# OptoBoard.net
KiCad netlist of a schematic drawn in Altium Designer
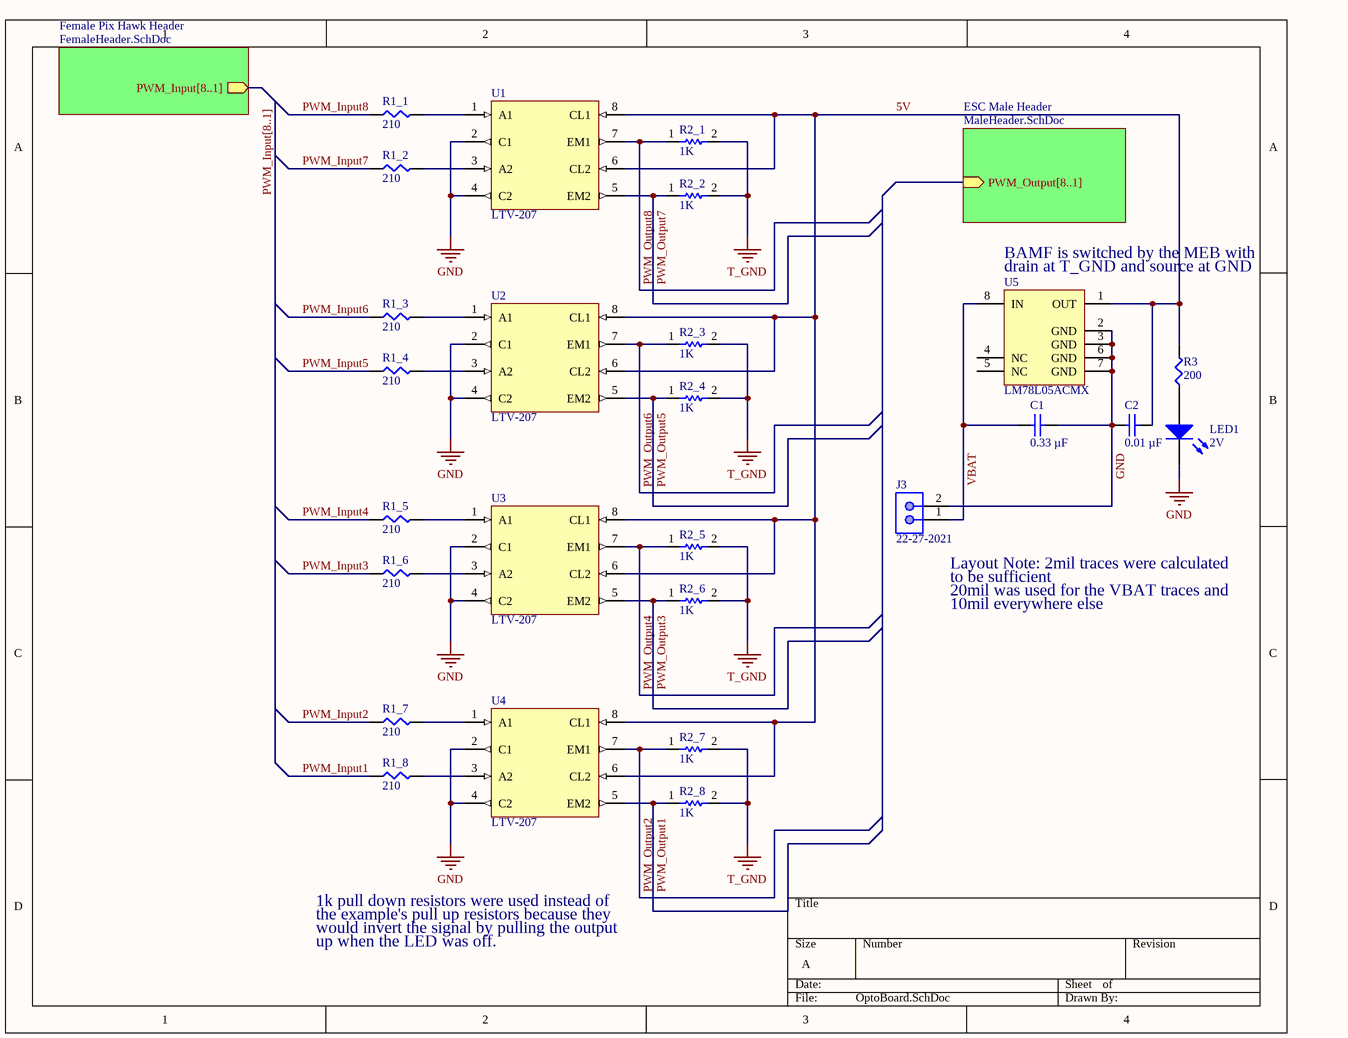
[diagram p0: OptoBoard.SchDoc]

(export (version "E")
  (design (tool "Eeschema 10.0.6"))
  (components
    (comp (ref "C1")
      (value "0.33 µF")
      (footprint "CAPC2013X95X45ML10T25")
      (description "±10% 50V Ceramic Capacitor X7R 0805 (2012 Metric)")
      (fields (field (name "MANUFACTURER") "Murata") (field (name "PART NUMBER") "GRM219R71H334KA88D"))
      (libsource (lib "Altium Content Vault") (part "CAP"))
    )
    (comp (ref "C2")
      (value "0.01 µF")
      (footprint "CAPC2013X70X45LL15T25")
      (description "±10% 100V Ceramic Capacitor X7R 0805 (2012 Metric)")
      (fields (field (name "MANUFACTURER") "Murata") (field (name "PART NUMBER") "GCM216R72A103KA37D"))
      (libsource (lib "Altium Content Vault") (part "CAP"))
    )
    (comp (ref "J3")
      (value "22-27-2021")
      (footprint "MOLX-22-27-2021_V")
      (fields
        (field (name "MANUFACTURER") "Molex")
        (field (name "PARTNUMBER") "0022272021")
        (field (name "MANUFACTURER PART NUMBER") "AE-6410-2A")
      )
      (libsource (lib "Altium Content Vault") (part "CN-1P-M-R2"))
    )
    (comp (ref "LED1")
      (value "2V")
      (footprint "1206  CYLINDRICAL- Reverse Use")
      (description "SMD mono-color reverse mount waterclear Chip LED, WL-SMRW, Red, 156120RS75300")
      (fields (field (name "MANUFACTURER") "Wuerth Elektronik") (field (name "PARTNUMBER") "156120RS75300"))
      (libsource (lib "Altium Content Vault") (part "WE-LED_K1A2-2"))
    )
    (comp (ref "R1_1")
      (value "210")
      (footprint "SMD-0805-RES")
      (description "RES SMD 210 OHM 1% 1/8W 0805")
      (fields (field (name "PART NUMBER") "ERJ-6ENF2100V") (field (name "DIGI-KEY PART NUMBER") "P210CCT-ND"))
      (libsource (lib "Panasonic_resistor_0805") (part "ERJ-6ENF2100V"))
    )
    (comp (ref "R1_2")
      (value "210")
      (footprint "SMD-0805-RES")
      (description "RES SMD 210 OHM 1% 1/8W 0805")
      (fields (field (name "PART NUMBER") "ERJ-6ENF2100V") (field (name "DIGI-KEY PART NUMBER") "P210CCT-ND"))
      (libsource (lib "Panasonic_resistor_0805") (part "ERJ-6ENF2100V"))
    )
    (comp (ref "R1_3")
      (value "210")
      (footprint "SMD-0805-RES")
      (description "RES SMD 210 OHM 1% 1/8W 0805")
      (fields (field (name "PART NUMBER") "ERJ-6ENF2100V") (field (name "DIGI-KEY PART NUMBER") "P210CCT-ND"))
      (libsource (lib "Panasonic_resistor_0805") (part "ERJ-6ENF2100V"))
    )
    (comp (ref "R1_4")
      (value "210")
      (footprint "SMD-0805-RES")
      (description "RES SMD 210 OHM 1% 1/8W 0805")
      (fields (field (name "PART NUMBER") "ERJ-6ENF2100V") (field (name "DIGI-KEY PART NUMBER") "P210CCT-ND"))
      (libsource (lib "Panasonic_resistor_0805") (part "ERJ-6ENF2100V"))
    )
    (comp (ref "R1_5")
      (value "210")
      (footprint "SMD-0805-RES")
      (description "RES SMD 210 OHM 1% 1/8W 0805")
      (fields (field (name "PART NUMBER") "ERJ-6ENF2100V") (field (name "DIGI-KEY PART NUMBER") "P210CCT-ND"))
      (libsource (lib "Panasonic_resistor_0805") (part "ERJ-6ENF2100V"))
    )
    (comp (ref "R1_6")
      (value "210")
      (footprint "SMD-0805-RES")
      (description "RES SMD 210 OHM 1% 1/8W 0805")
      (fields (field (name "PART NUMBER") "ERJ-6ENF2100V") (field (name "DIGI-KEY PART NUMBER") "P210CCT-ND"))
      (libsource (lib "Panasonic_resistor_0805") (part "ERJ-6ENF2100V"))
    )
    (comp (ref "R1_7")
      (value "210")
      (footprint "SMD-0805-RES")
      (description "RES SMD 210 OHM 1% 1/8W 0805")
      (fields (field (name "PART NUMBER") "ERJ-6ENF2100V") (field (name "DIGI-KEY PART NUMBER") "P210CCT-ND"))
      (libsource (lib "Panasonic_resistor_0805") (part "ERJ-6ENF2100V"))
    )
    (comp (ref "R1_8")
      (value "210")
      (footprint "SMD-0805-RES")
      (description "RES SMD 210 OHM 1% 1/8W 0805")
      (fields (field (name "PART NUMBER") "ERJ-6ENF2100V") (field (name "DIGI-KEY PART NUMBER") "P210CCT-ND"))
      (libsource (lib "Panasonic_resistor_0805") (part "ERJ-6ENF2100V"))
    )
    (comp (ref "R2_1")
      (value "1K")
      (footprint "RESC2013X60X35ML10T20")
      (description "Chip Resistor, 1 KOhm, +/- 1%, 125 mW, -55 to 155 degC, 0805 (2012 Metric), RoHS, Tape and Reel")
      (fields (field (name "TOLERANCE") "1%") (field (name "MANUFACTURER") "Yageo"))
      (libsource (lib "Altium Content Vault") (part "RES-2"))
    )
    (comp (ref "R2_2")
      (value "1K")
      (footprint "RESC2013X60X35ML10T20")
      (description "Chip Resistor, 1 KOhm, +/- 1%, 125 mW, -55 to 155 degC, 0805 (2012 Metric), RoHS, Tape and Reel")
      (fields (field (name "TOLERANCE") "1%") (field (name "MANUFACTURER") "Yageo"))
      (libsource (lib "Altium Content Vault") (part "RES-2"))
    )
    (comp (ref "R2_3")
      (value "1K")
      (footprint "RESC2013X60X35ML10T20")
      (description "Chip Resistor, 1 KOhm, +/- 1%, 125 mW, -55 to 155 degC, 0805 (2012 Metric), RoHS, Tape and Reel")
      (fields (field (name "TOLERANCE") "1%") (field (name "MANUFACTURER") "Yageo"))
      (libsource (lib "Altium Content Vault") (part "RES-2"))
    )
    (comp (ref "R2_4")
      (value "1K")
      (footprint "RESC2013X60X35ML10T20")
      (description "Chip Resistor, 1 KOhm, +/- 1%, 125 mW, -55 to 155 degC, 0805 (2012 Metric), RoHS, Tape and Reel")
      (fields (field (name "TOLERANCE") "1%") (field (name "MANUFACTURER") "Yageo"))
      (libsource (lib "Altium Content Vault") (part "RES-2"))
    )
    (comp (ref "R2_5")
      (value "1K")
      (footprint "RESC2013X60X35ML10T20")
      (description "Chip Resistor, 1 KOhm, +/- 1%, 125 mW, -55 to 155 degC, 0805 (2012 Metric), RoHS, Tape and Reel")
      (fields (field (name "TOLERANCE") "1%") (field (name "MANUFACTURER") "Yageo"))
      (libsource (lib "Altium Content Vault") (part "RES-2"))
    )
    (comp (ref "R2_6")
      (value "1K")
      (footprint "RESC2013X60X35ML10T20")
      (description "Chip Resistor, 1 KOhm, +/- 1%, 125 mW, -55 to 155 degC, 0805 (2012 Metric), RoHS, Tape and Reel")
      (fields (field (name "TOLERANCE") "1%") (field (name "MANUFACTURER") "Yageo"))
      (libsource (lib "Altium Content Vault") (part "RES-2"))
    )
    (comp (ref "R2_7")
      (value "1K")
      (footprint "RESC2013X60X35ML10T20")
      (description "Chip Resistor, 1 KOhm, +/- 1%, 125 mW, -55 to 155 degC, 0805 (2012 Metric), RoHS, Tape and Reel")
      (fields (field (name "TOLERANCE") "1%") (field (name "MANUFACTURER") "Yageo"))
      (libsource (lib "Altium Content Vault") (part "RES-2"))
    )
    (comp (ref "R2_8")
      (value "1K")
      (footprint "RESC2013X60X35ML10T20")
      (description "Chip Resistor, 1 KOhm, +/- 1%, 125 mW, -55 to 155 degC, 0805 (2012 Metric), RoHS, Tape and Reel")
      (fields (field (name "TOLERANCE") "1%") (field (name "MANUFACTURER") "Yageo"))
      (libsource (lib "Altium Content Vault") (part "RES-2"))
    )
    (comp (ref "R3")
      (value "200")
      (footprint "SMD-0805-RES")
      (description "RES SMD 200 OHM 1% 1/8W 0805")
      (fields (field (name "PART NUMBER") "ERJ-6ENF2000V") (field (name "DIGI-KEY PART NUMBER") "P200CCT-ND"))
      (libsource (lib "Panasonic_resistor_0805") (part "ERJ-6ENF2000V"))
    )
    (comp (ref "U1")
      (value "LTV-207")
      (footprint "ZMDI-SOP-8_N")
      (description "Transistor Output Optocouplers SO8 100-200% 3.75KV 2CH Optocoupler")
      (fields (field (name "MANUFACTURER") "Lite-On Inc."))
      (libsource (lib "Altium Content Vault") (part "ZMDI-ZLED7010-SOP8"))
    )
    (comp (ref "U2")
      (value "LTV-207")
      (footprint "ZMDI-SOP-8_N")
      (description "Transistor Output Optocouplers SO8 100-200% 3.75KV 2CH Optocoupler")
      (fields (field (name "MANUFACTURER") "Lite-On Inc."))
      (libsource (lib "Altium Content Vault") (part "ZMDI-ZLED7010-SOP8"))
    )
    (comp (ref "U3")
      (value "LTV-207")
      (footprint "ZMDI-SOP-8_N")
      (description "Transistor Output Optocouplers SO8 100-200% 3.75KV 2CH Optocoupler")
      (fields (field (name "MANUFACTURER") "Lite-On Inc."))
      (libsource (lib "Altium Content Vault") (part "ZMDI-ZLED7010-SOP8"))
    )
    (comp (ref "U4")
      (value "LTV-207")
      (footprint "ZMDI-SOP-8_N")
      (description "Transistor Output Optocouplers SO8 100-200% 3.75KV 2CH Optocoupler")
      (fields (field (name "MANUFACTURER") "Lite-On Inc."))
      (libsource (lib "Altium Content Vault") (part "ZMDI-ZLED7010-SOP8"))
    )
    (comp (ref "U5")
      (value "LM78L05ACMX")
      (footprint "D0008A_N")
      (description "3-Terminal Positive Regulator, 5 Vout, 8-pin Narrow SOIC, 2500 Reel")
      (fields (field (name "MANUFACTURER") "Texas Instruments"))
      (libsource (lib "Altium Content Vault") (part "PM-REG-LM78L05-IL8"))
    )
  )
  (nets
    (net (code "1") (name "/5V") (class "Default")
      (node (ref "C2") (pin "2") (pinfunction "2_2") (pintype "passive"))
      (node (ref "R3") (pin "2") (pinfunction "2_2") (pintype "passive"))
      (node (ref "U1") (pin "6") (pinfunction "CL2_6") (pintype "input"))
      (node (ref "U1") (pin "8") (pinfunction "CL1_8") (pintype "input"))
      (node (ref "U2") (pin "6") (pinfunction "CL2_6") (pintype "input"))
      (node (ref "U2") (pin "8") (pinfunction "CL1_8") (pintype "input"))
      (node (ref "U3") (pin "6") (pinfunction "CL2_6") (pintype "input"))
      (node (ref "U3") (pin "8") (pinfunction "CL1_8") (pintype "input"))
      (node (ref "U4") (pin "6") (pinfunction "CL2_6") (pintype "input"))
      (node (ref "U4") (pin "8") (pinfunction "CL1_8") (pintype "input"))
      (node (ref "U5") (pin "1") (pinfunction "OUT_1") (pintype "power_in"))
    )
    (net (code "2") (name "/PWM_Input1") (class "Default")
      (node (ref "R1_8") (pin "1") (pinfunction "1_1") (pintype "passive"))
    )
    (net (code "3") (name "/PWM_Input2") (class "Default")
      (node (ref "R1_7") (pin "1") (pinfunction "1_1") (pintype "passive"))
    )
    (net (code "4") (name "/PWM_Input3") (class "Default")
      (node (ref "R1_6") (pin "1") (pinfunction "1_1") (pintype "passive"))
    )
    (net (code "5") (name "/PWM_Input4") (class "Default")
      (node (ref "R1_5") (pin "1") (pinfunction "1_1") (pintype "passive"))
    )
    (net (code "6") (name "/PWM_Input5") (class "Default")
      (node (ref "R1_4") (pin "1") (pinfunction "1_1") (pintype "passive"))
    )
    (net (code "7") (name "/PWM_Input6") (class "Default")
      (node (ref "R1_3") (pin "1") (pinfunction "1_1") (pintype "passive"))
    )
    (net (code "8") (name "/PWM_Input7") (class "Default")
      (node (ref "R1_2") (pin "1") (pinfunction "1_1") (pintype "passive"))
    )
    (net (code "9") (name "/PWM_Input8") (class "Default")
      (node (ref "R1_1") (pin "1") (pinfunction "1_1") (pintype "passive"))
    )
    (net (code "11") (name "/PWM_Output1") (class "Default")
      (node (ref "R2_8") (pin "1") (pinfunction "1_1") (pintype "passive"))
      (node (ref "U4") (pin "5") (pinfunction "EM2_5") (pintype "output"))
    )
    (net (code "12") (name "/PWM_Output2") (class "Default")
      (node (ref "R2_7") (pin "1") (pinfunction "1_1") (pintype "passive"))
      (node (ref "U4") (pin "7") (pinfunction "EM1_7") (pintype "output"))
    )
    (net (code "13") (name "/PWM_Output3") (class "Default")
      (node (ref "R2_6") (pin "1") (pinfunction "1_1") (pintype "passive"))
      (node (ref "U3") (pin "5") (pinfunction "EM2_5") (pintype "output"))
    )
    (net (code "14") (name "/PWM_Output4") (class "Default")
      (node (ref "R2_5") (pin "1") (pinfunction "1_1") (pintype "passive"))
      (node (ref "U3") (pin "7") (pinfunction "EM1_7") (pintype "output"))
    )
    (net (code "15") (name "/PWM_Output5") (class "Default")
      (node (ref "R2_4") (pin "1") (pinfunction "1_1") (pintype "passive"))
      (node (ref "U2") (pin "5") (pinfunction "EM2_5") (pintype "output"))
    )
    (net (code "16") (name "/PWM_Output6") (class "Default")
      (node (ref "R2_3") (pin "1") (pinfunction "1_1") (pintype "passive"))
      (node (ref "U2") (pin "7") (pinfunction "EM1_7") (pintype "output"))
    )
    (net (code "17") (name "/PWM_Output7") (class "Default")
      (node (ref "R2_2") (pin "1") (pinfunction "1_1") (pintype "passive"))
      (node (ref "U1") (pin "5") (pinfunction "EM2_5") (pintype "output"))
    )
    (net (code "18") (name "/PWM_Output8") (class "Default")
      (node (ref "R2_1") (pin "1") (pinfunction "1_1") (pintype "passive"))
      (node (ref "U1") (pin "7") (pinfunction "EM1_7") (pintype "output"))
    )
    (net (code "20") (name "/VBAT") (class "Default")
      (node (ref "C1") (pin "1") (pinfunction "1_1") (pintype "passive"))
      (node (ref "J3") (pin "1") (pinfunction "1_1") (pintype "passive"))
      (node (ref "U5") (pin "8") (pinfunction "IN_8") (pintype "power_in"))
    )
    (net (code "21") (name "GND") (class "Default")
      (node (ref "C1") (pin "2") (pinfunction "2_2") (pintype "passive"))
      (node (ref "C2") (pin "1") (pinfunction "1_1") (pintype "passive"))
      (node (ref "J3") (pin "2") (pinfunction "2_2") (pintype "passive"))
      (node (ref "LED1") (pin "1") (pinfunction "K_1") (pintype "passive"))
      (node (ref "U1") (pin "2") (pinfunction "C1_2") (pintype "output"))
      (node (ref "U1") (pin "4") (pinfunction "C2_4") (pintype "output"))
      (node (ref "U2") (pin "2") (pinfunction "C1_2") (pintype "output"))
      (node (ref "U2") (pin "4") (pinfunction "C2_4") (pintype "output"))
      (node (ref "U3") (pin "2") (pinfunction "C1_2") (pintype "output"))
      (node (ref "U3") (pin "4") (pinfunction "C2_4") (pintype "output"))
      (node (ref "U4") (pin "2") (pinfunction "C1_2") (pintype "output"))
      (node (ref "U4") (pin "4") (pinfunction "C2_4") (pintype "output"))
      (node (ref "U5") (pin "2") (pinfunction "GND_2") (pintype "power_in"))
      (node (ref "U5") (pin "3") (pinfunction "GND_3") (pintype "power_in"))
      (node (ref "U5") (pin "6") (pinfunction "GND_6") (pintype "power_in"))
      (node (ref "U5") (pin "7") (pinfunction "GND_7") (pintype "power_in"))
    )
    (net (code "22") (name "Net-(LED1-A)") (class "Default")
      (node (ref "LED1") (pin "2") (pinfunction "A_2") (pintype "passive"))
      (node (ref "R3") (pin "1") (pinfunction "1_1") (pintype "passive"))
    )
    (net (code "23") (name "Net-(U1-A1)") (class "Default")
      (node (ref "R1_1") (pin "2") (pinfunction "2_2") (pintype "passive"))
      (node (ref "U1") (pin "1") (pinfunction "A1_1") (pintype "input"))
    )
    (net (code "24") (name "Net-(U1-A2)") (class "Default")
      (node (ref "R1_2") (pin "2") (pinfunction "2_2") (pintype "passive"))
      (node (ref "U1") (pin "3") (pinfunction "A2_3") (pintype "input"))
    )
    (net (code "25") (name "Net-(U2-A1)") (class "Default")
      (node (ref "R1_3") (pin "2") (pinfunction "2_2") (pintype "passive"))
      (node (ref "U2") (pin "1") (pinfunction "A1_1") (pintype "input"))
    )
    (net (code "26") (name "Net-(U2-A2)") (class "Default")
      (node (ref "R1_4") (pin "2") (pinfunction "2_2") (pintype "passive"))
      (node (ref "U2") (pin "3") (pinfunction "A2_3") (pintype "input"))
    )
    (net (code "27") (name "Net-(U3-A1)") (class "Default")
      (node (ref "R1_5") (pin "2") (pinfunction "2_2") (pintype "passive"))
      (node (ref "U3") (pin "1") (pinfunction "A1_1") (pintype "input"))
    )
    (net (code "28") (name "Net-(U3-A2)") (class "Default")
      (node (ref "R1_6") (pin "2") (pinfunction "2_2") (pintype "passive"))
      (node (ref "U3") (pin "3") (pinfunction "A2_3") (pintype "input"))
    )
    (net (code "29") (name "Net-(U4-A1)") (class "Default")
      (node (ref "R1_7") (pin "2") (pinfunction "2_2") (pintype "passive"))
      (node (ref "U4") (pin "1") (pinfunction "A1_1") (pintype "input"))
    )
    (net (code "30") (name "Net-(U4-A2)") (class "Default")
      (node (ref "R1_8") (pin "2") (pinfunction "2_2") (pintype "passive"))
      (node (ref "U4") (pin "3") (pinfunction "A2_3") (pintype "input"))
    )
    (net (code "31") (name "T_GND") (class "Default")
      (node (ref "R2_1") (pin "2") (pinfunction "2_2") (pintype "passive"))
      (node (ref "R2_2") (pin "2") (pinfunction "2_2") (pintype "passive"))
      (node (ref "R2_3") (pin "2") (pinfunction "2_2") (pintype "passive"))
      (node (ref "R2_4") (pin "2") (pinfunction "2_2") (pintype "passive"))
      (node (ref "R2_5") (pin "2") (pinfunction "2_2") (pintype "passive"))
      (node (ref "R2_6") (pin "2") (pinfunction "2_2") (pintype "passive"))
      (node (ref "R2_7") (pin "2") (pinfunction "2_2") (pintype "passive"))
      (node (ref "R2_8") (pin "2") (pinfunction "2_2") (pintype "passive"))
    )
    (net (code "32") (name "unconnected-(U5-NC-Pad4)") (class "Default")
      (node (ref "U5") (pin "4") (pinfunction "NC_4") (pintype "passive"))
    )
    (net (code "33") (name "unconnected-(U5-NC-Pad5)") (class "Default")
      (node (ref "U5") (pin "5") (pinfunction "NC_5") (pintype "passive"))
    )
  )
)
